# 3102_Sheet.net
KiCad netlist of a schematic drawn in Altium Designer
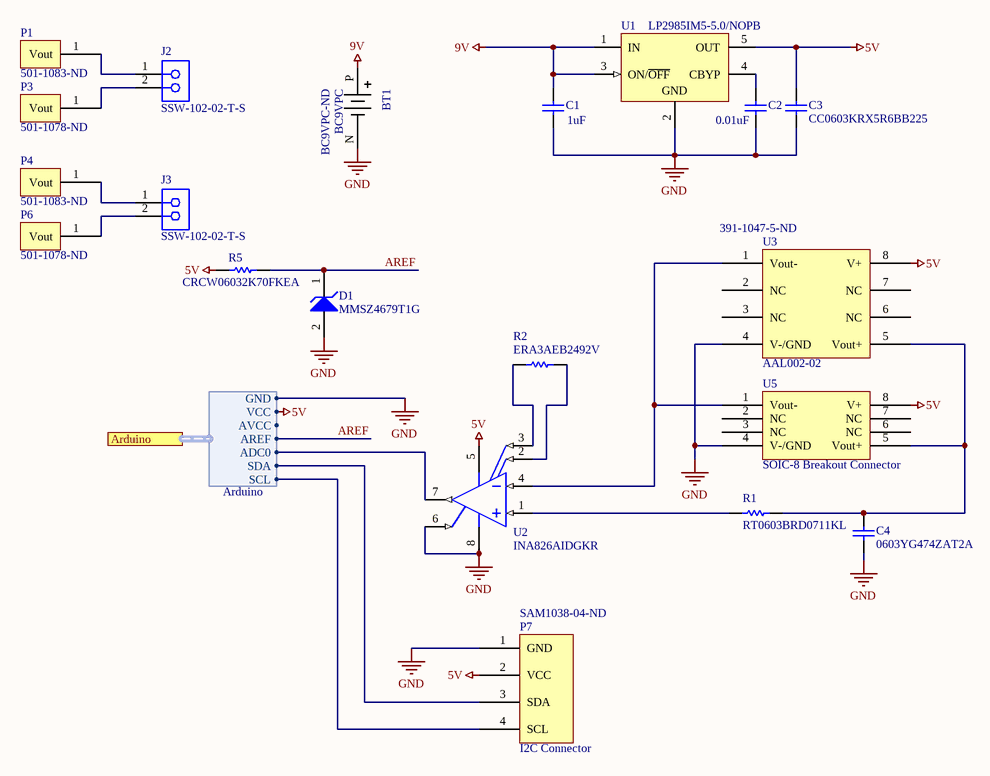
[diagram p0: 3102_Sheet.SchDoc]

(export (version "E")
  (design (tool "Eeschema 10.0.6"))
  (components
    (comp (ref "BT1")
      (value "BC9VPC")
      (footprint "*BAT_BC9VPC_BC9VPC(Primary)")
      (description "BATTERY HOLDER 9V PC PIN")
      (fields
        (field (name "MF") "MPD")
        (field (name "SUPPLIER PART NUMBER 1") "BC9VPC-ND")
        (field (name "MANUFACTURER") "Memory Protection Devices")
      )
      (libsource (lib "BC9VPC") (part "BC9VPC"))
    )
    (comp (ref "C1")
      (value "1uF")
      (footprint "CAPC1608X90X30LL10T20")
      (description "Chip Capacitor, 1 uF, +/- 10%, 16 V, -55 to 125 degC, 0603 (1608 Metric), RoHS, Tape and Reel")
      (fields (field (name "MANUFACTURER") "Samsung Electro-Mechanics"))
      (libsource (lib "Altium Content Vault") (part "CAP-NP-2"))
    )
    (comp (ref "C2")
      (value "0.01uF")
      (footprint "CAPC1613X90X50LL10T25")
      (fields (field (name "PART NUMBER") "CC0603KPX7R9BB103") (field (name "MANUFACTURER") "Yageo"))
      (libsource (lib "Altium Content Vault") (part "CAP"))
    )
    (comp (ref "C3")
      (value "CC0603KRX5R6BB225")
      (footprint "CAPC1608X90X40LL10T20")
      (fields (field (name "MANUFACTURER") "Yageo") (field (name "TOLERANCE") "±10%"))
      (libsource (lib "Altium Content Vault") (part "CAP-NP-2"))
    )
    (comp (ref "C4")
      (value "0603YG474ZAT2A")
      (footprint "CAPC1608X90X35ML15T15")
      (fields (field (name "MANUFACTURER") "AVX Interconnect / Elco"))
      (libsource (lib "Altium Content Vault") (part "CAP"))
    )
    (comp (ref "D1")
      (value "MMSZ4679T1G")
      (footprint "ONSC-SOD-123-2-425-04_V")
      (description "Zener Voltage Regulator, 500 mW, 2-Pin SOD-123, Pb-Free, Tape and Reel")
      (fields (field (name "MANUFACTURER") "On Semiconductor"))
      (libsource (lib "Altium Content Vault") (part "ONSC-K1A2-2"))
    )
    (comp (ref "J2")
      (value "SSW-102-02-T-S")
      (footprint "SMTC-SSW-102-02-X-S")
      (description "SQ Post Socket, Through-hole, Vertical, -55 to 105 degC, 2.54 mm Pitch, 2-Pin, Female, RoHS")
      (fields (field (name "MANUFACTURER") "Samtec"))
      (libsource (lib "Altium Content Vault") (part "SMTC-SSW-102-02-X-S-X"))
    )
    (comp (ref "J3")
      (value "SSW-102-02-T-S")
      (footprint "SMTC-SSW-102-02-X-S")
      (description "SQ Post Socket, Through-hole, Vertical, -55 to 105 degC, 2.54 mm Pitch, 2-Pin, Female, RoHS")
      (fields (field (name "MANUFACTURER") "Samtec"))
      (libsource (lib "Altium Content Vault") (part "SMTC-SSW-102-02-X-S-X"))
    )
    (comp (ref "P1")
      (value "Model 1581 Red")
      (footprint "Banana Jack Footprint")
      (description "Pomona Model 1581")
      (fields (field (name "SUPPLIER PART NUMBER 1") "501-1083-ND"))
      (libsource (lib "Schlib") (part "Banana Plug"))
    )
    (comp (ref "P3")
      (value "Model 1581 Black")
      (footprint "Banana Jack Footprint")
      (description "Pomona Model 1581")
      (fields (field (name "SUPPLIER PART NUMBER 1") "501-1078-ND"))
      (libsource (lib "Schlib") (part "Banana Plug"))
    )
    (comp (ref "P4")
      (value "Model 1581 Red")
      (footprint "Banana Jack Footprint")
      (description "Pomona Model 1581")
      (fields (field (name "SUPPLIER PART NUMBER 1") "501-1083-ND"))
      (libsource (lib "Schlib") (part "Banana Plug"))
    )
    (comp (ref "P6")
      (value "Model 1581 Black")
      (footprint "Banana Jack Footprint")
      (description "Pomona Model 1581")
      (fields (field (name "SUPPLIER PART NUMBER 1") "501-1078-ND"))
      (libsource (lib "Schlib") (part "Banana Plug"))
    )
    (comp (ref "P7")
      (value "I2C Connector")
      (footprint "HDR1X4")
      (description "SAMTEC - TSW-104-08-G-S - HEADER, 2.54MM, THT VERT, 4WAY")
      (fields
        (field (name "SUPPLIER PART NUMBER 1") "SAM1038-04-ND")
        (field (name "MANUFACTURER") "Samtec")
        (field (name "MANUFACTURER PART NUMBER") "TSW-104-08-G-S")
      )
      (libsource (lib "Schlib") (part "I2C Connector"))
    )
    (comp (ref "R1")
      (value "Res3")
      (footprint "J1-0603")
      (fields (field (name "MANUFACTURER") "Yageo") (field (name "PART NUMBER") "RT0603BRD0711KL"))
      (libsource (lib "Altium Content Vault") (part "RES"))
    )
    (comp (ref "R2")
      (value "ERA3AEB2492V")
      (footprint "RESC1608X55X30NL20T20")
      (description "CRCW06032K67FKEA")
      (fields (field (name "MANUFACTURER") "Vishay Dale"))
      (libsource (lib "Altium Content Vault") (part "RES"))
    )
    (comp (ref "R5")
      (value "CRCW06032K70FKEA")
      (footprint "RESC1609X50X30ML10T20")
      (fields (field (name "MANUFACTURER") "Vishay Dale"))
      (libsource (lib "Altium Content Vault") (part "RES"))
    )
    (comp (ref "U1")
      (value "LP2985IM5-5.0/NOPB")
      (footprint "DBV0005A_L")
      (description "Micropower 150 mA Low-Noise Ultra Low-Dropout Regulator, 5-pin SOT-23, Pb-Free")
      (fields (field (name "MANUFACTURER") "Texas Instruments"))
      (libsource (lib "Altium Content Vault") (part "PM-REG-LP2985-SOT5"))
    )
    (comp (ref "U2")
      (value "INA826AIDGKR")
      (footprint "DGK0008A_N")
      (fields (field (name "MANUFACTURER") "Texas Instruments"))
      (libsource (lib "Altium Content Vault") (part "TI-INA826X8"))
    )
    (comp (ref "U3")
      (value "AAL002-02")
      (footprint "SO8_N")
      (description "Sensor Magmtr Wheat Brdg 8SOIC")
      (fields
        (field (name "SUPPLIER PART NUMBER 1") "391-1047-5-ND")
        (field (name "MANUFACTURER") "NVE")
        (field (name "MANUFACTURER PART NUMBER") "AAL002-02E")
      )
      (libsource (lib "Schlib") (part "AAL002-02"))
    )
    (comp (ref "U5")
      (value "SOIC-8 Breakout Connector")
      (footprint "SOIC-8 Breakout Board")
      (libsource (lib "Schlib") (part "SOIC-8 Breakout Connector"))
    )
  )
  (nets
    (net (code "2") (name "/ADC0") (class "Default")
      (node (ref "U2") (pin "7") (pinfunction "VOUT_7") (pintype "output"))
    )
    (net (code "3") (name "/AREF") (class "Default")
      (node (ref "D1") (pin "1") (pinfunction "K_1") (pintype "passive"))
      (node (ref "R5") (pin "2") (pinfunction "2_2") (pintype "passive"))
    )
    (net (code "4") (name "/SCL") (class "Default")
      (node (ref "P7") (pin "4") (pinfunction "SCL_4") (pintype "passive"))
    )
    (net (code "5") (name "/SDA") (class "Default")
      (node (ref "P7") (pin "3") (pinfunction "SDA_3") (pintype "passive"))
    )
    (net (code "7") (name "5V") (class "Default")
      (node (ref "C3") (pin "2") (pinfunction "2_2") (pintype "passive"))
      (node (ref "P7") (pin "2") (pinfunction "VCC_2") (pintype "passive"))
      (node (ref "R5") (pin "1") (pinfunction "1_1") (pintype "passive"))
      (node (ref "U1") (pin "5") (pinfunction "OUT_5") (pintype "power_in"))
      (node (ref "U2") (pin "5") (pinfunction "VS-_5") (pintype "power_in"))
      (node (ref "U3") (pin "8") (pinfunction "V+_8") (pintype "passive"))
      (node (ref "U5") (pin "8") (pinfunction "V+_8") (pintype "passive"))
    )
    (net (code "8") (name "9V") (class "Default")
      (node (ref "BT1") (pin "P") (pinfunction "POS_P") (pintype "passive"))
      (node (ref "C1") (pin "1") (pinfunction "1_1") (pintype "passive"))
      (node (ref "U1") (pin "1") (pinfunction "IN_1") (pintype "power_in"))
      (node (ref "U1") (pin "3") (pinfunction "ON/~{OFF}_3") (pintype "input"))
    )
    (net (code "9") (name "GND") (class "Default")
      (node (ref "BT1") (pin "N") (pinfunction "NEG_N") (pintype "passive"))
      (node (ref "C1") (pin "2") (pinfunction "2_2") (pintype "passive"))
      (node (ref "C2") (pin "1") (pinfunction "1_1") (pintype "passive"))
      (node (ref "C3") (pin "1") (pinfunction "1_1") (pintype "passive"))
      (node (ref "C4") (pin "1") (pinfunction "1_1") (pintype "passive"))
      (node (ref "D1") (pin "2") (pinfunction "A_2") (pintype "passive"))
      (node (ref "P7") (pin "1") (pinfunction "GND_1") (pintype "passive"))
      (node (ref "U1") (pin "2") (pinfunction "GND_2") (pintype "power_in"))
      (node (ref "U2") (pin "6") (pinfunction "REF_6") (pintype "input"))
      (node (ref "U2") (pin "8") (pinfunction "VS+_8") (pintype "power_in"))
      (node (ref "U3") (pin "4") (pinfunction "V-/GND_4") (pintype "passive"))
      (node (ref "U5") (pin "4") (pinfunction "V-/GND_4") (pintype "passive"))
    )
    (net (code "10") (name "Net-(P1-Vout)") (class "Default")
      (node (ref "J2") (pin "1") (pinfunction "1_1") (pintype "passive"))
      (node (ref "P1") (pin "1") (pinfunction "Vout_1") (pintype "passive"))
    )
    (net (code "11") (name "Net-(P3-Vout)") (class "Default")
      (node (ref "J2") (pin "2") (pinfunction "2_2") (pintype "passive"))
      (node (ref "P3") (pin "1") (pinfunction "Vout_1") (pintype "passive"))
    )
    (net (code "12") (name "Net-(P4-Vout)") (class "Default")
      (node (ref "J3") (pin "1") (pinfunction "1_1") (pintype "passive"))
      (node (ref "P4") (pin "1") (pinfunction "Vout_1") (pintype "passive"))
    )
    (net (code "13") (name "Net-(P6-Vout)") (class "Default")
      (node (ref "J3") (pin "2") (pinfunction "2_2") (pintype "passive"))
      (node (ref "P6") (pin "1") (pinfunction "Vout_1") (pintype "passive"))
    )
    (net (code "14") (name "Net-(R2-Pad1)") (class "Default")
      (node (ref "R2") (pin "1") (pinfunction "1_1") (pintype "passive"))
      (node (ref "U2") (pin "2") (pinfunction "RG_2") (pintype "input"))
    )
    (net (code "15") (name "Net-(R2-Pad2)") (class "Default")
      (node (ref "R2") (pin "2") (pinfunction "2_2") (pintype "passive"))
      (node (ref "U2") (pin "3") (pinfunction "RG_3") (pintype "input"))
    )
    (net (code "16") (name "Net-(U1-CBYP)") (class "Default")
      (node (ref "C2") (pin "2") (pinfunction "2_2") (pintype "passive"))
      (node (ref "U1") (pin "4") (pinfunction "CBYP_4") (pintype "passive"))
    )
    (net (code "17") (name "Net-(U2-IN+)") (class "Default")
      (node (ref "U2") (pin "4") (pinfunction "IN+_4") (pintype "input"))
      (node (ref "U3") (pin "1") (pinfunction "Vout-_1") (pintype "passive"))
      (node (ref "U5") (pin "1") (pinfunction "Vout-_1") (pintype "passive"))
    )
    (net (code "18") (name "Net-(U2-IN-)") (class "Default")
      (node (ref "R1") (pin "1") (pinfunction "1_1") (pintype "passive"))
      (node (ref "U2") (pin "1") (pinfunction "IN-_1") (pintype "input"))
    )
    (net (code "19") (name "Net-(U3-Vout+)") (class "Default")
      (node (ref "C4") (pin "2") (pinfunction "2_2") (pintype "passive"))
      (node (ref "R1") (pin "2") (pinfunction "2_2") (pintype "passive"))
      (node (ref "U3") (pin "5") (pinfunction "Vout+_5") (pintype "passive"))
      (node (ref "U5") (pin "5") (pinfunction "Vout+_5") (pintype "passive"))
    )
    (net (code "20") (name "unconnected-(U3-NC-Pad2)") (class "Default")
      (node (ref "U3") (pin "2") (pinfunction "NC_2") (pintype "passive"))
    )
    (net (code "21") (name "unconnected-(U3-NC-Pad3)") (class "Default")
      (node (ref "U3") (pin "3") (pinfunction "NC_3") (pintype "passive"))
    )
    (net (code "22") (name "unconnected-(U3-NC-Pad6)") (class "Default")
      (node (ref "U3") (pin "6") (pinfunction "NC_6") (pintype "passive"))
    )
    (net (code "23") (name "unconnected-(U3-NC-Pad7)") (class "Default")
      (node (ref "U3") (pin "7") (pinfunction "NC_7") (pintype "passive"))
    )
    (net (code "24") (name "unconnected-(U5-NC-Pad2)") (class "Default")
      (node (ref "U5") (pin "2") (pinfunction "NC_2") (pintype "passive"))
    )
    (net (code "25") (name "unconnected-(U5-NC-Pad3)") (class "Default")
      (node (ref "U5") (pin "3") (pinfunction "NC_3") (pintype "passive"))
    )
    (net (code "26") (name "unconnected-(U5-NC-Pad6)") (class "Default")
      (node (ref "U5") (pin "6") (pinfunction "NC_6") (pintype "passive"))
    )
    (net (code "27") (name "unconnected-(U5-NC-Pad7)") (class "Default")
      (node (ref "U5") (pin "7") (pinfunction "NC_7") (pintype "passive"))
    )
  )
)
